# VoltageMonitor.net
KiCad netlist of a schematic drawn in Altium Designer
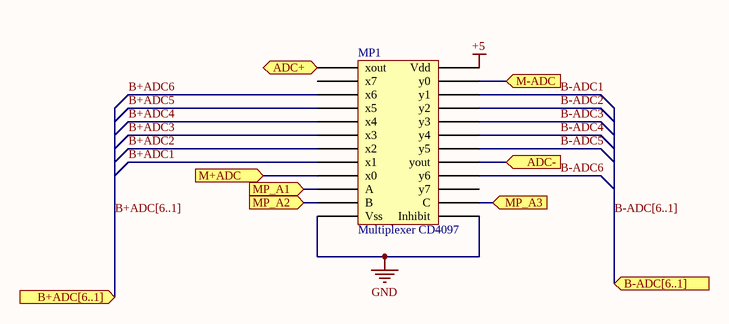
[diagram p0: VoltageMonitor.SchDoc]

(export (version "E")
  (design (tool "Eeschema 10.0.6"))
  (components
    (comp (ref "MP1")
      (value "Multiplexer CD4097")
      (footprint "SOIC24")
      (libsource (lib "Custom") (part "Multiplexer CD4097"))
    )
  )
  (nets
    (net (code "1") (name "+5") (class "Default")
      (node (ref "MP1") (pin "Vdd") (pinfunction "Vdd_Vdd") (pintype "passive"))
    )
    (net (code "2") (name "/ADC+") (class "Default")
      (node (ref "MP1") (pin "xout") (pinfunction "xout_xout") (pintype "passive"))
    )
    (net (code "3") (name "/ADC-") (class "Default")
      (node (ref "MP1") (pin "yout") (pinfunction "yout_yout") (pintype "passive"))
    )
    (net (code "4") (name "/B+ADC1") (class "Default")
      (node (ref "MP1") (pin "x1") (pinfunction "x1_x1") (pintype "passive"))
    )
    (net (code "5") (name "/B+ADC2") (class "Default")
      (node (ref "MP1") (pin "x2") (pinfunction "x2_x2") (pintype "passive"))
    )
    (net (code "6") (name "/B+ADC3") (class "Default")
      (node (ref "MP1") (pin "x3") (pinfunction "x3_x3") (pintype "passive"))
    )
    (net (code "7") (name "/B+ADC4") (class "Default")
      (node (ref "MP1") (pin "x4") (pinfunction "x4_x4") (pintype "passive"))
    )
    (net (code "8") (name "/B+ADC5") (class "Default")
      (node (ref "MP1") (pin "x5") (pinfunction "x5_x5") (pintype "passive"))
    )
    (net (code "9") (name "/B+ADC6") (class "Default")
      (node (ref "MP1") (pin "x6") (pinfunction "x6_x6") (pintype "passive"))
    )
    (net (code "11") (name "/B-ADC1") (class "Default")
      (node (ref "MP1") (pin "y1") (pinfunction "y1_y1") (pintype "passive"))
    )
    (net (code "12") (name "/B-ADC2") (class "Default")
      (node (ref "MP1") (pin "y2") (pinfunction "y2_y2") (pintype "passive"))
    )
    (net (code "13") (name "/B-ADC3") (class "Default")
      (node (ref "MP1") (pin "y3") (pinfunction "y3_y3") (pintype "passive"))
    )
    (net (code "14") (name "/B-ADC4") (class "Default")
      (node (ref "MP1") (pin "y4") (pinfunction "y4_y4") (pintype "passive"))
    )
    (net (code "15") (name "/B-ADC5") (class "Default")
      (node (ref "MP1") (pin "y5") (pinfunction "y5_y5") (pintype "passive"))
    )
    (net (code "16") (name "/B-ADC6") (class "Default")
      (node (ref "MP1") (pin "y6") (pinfunction "y6_y6") (pintype "passive"))
    )
    (net (code "18") (name "/M+ADC") (class "Default")
      (node (ref "MP1") (pin "x0") (pinfunction "x0_x0") (pintype "passive"))
    )
    (net (code "19") (name "/M-ADC") (class "Default")
      (node (ref "MP1") (pin "y0") (pinfunction "y0_y0") (pintype "passive"))
    )
    (net (code "20") (name "/MP_A1") (class "Default")
      (node (ref "MP1") (pin "A") (pinfunction "A_A") (pintype "passive"))
    )
    (net (code "21") (name "/MP_A2") (class "Default")
      (node (ref "MP1") (pin "B") (pinfunction "B_B") (pintype "passive"))
    )
    (net (code "22") (name "/MP_A3") (class "Default")
      (node (ref "MP1") (pin "C") (pinfunction "C_C") (pintype "passive"))
    )
    (net (code "23") (name "GND") (class "Default")
      (node (ref "MP1") (pin "Inhibit") (pinfunction "Inhibit_Inhibit") (pintype "passive"))
      (node (ref "MP1") (pin "Vss") (pinfunction "Vss_Vss") (pintype "passive"))
    )
    (net (code "24") (name "unconnected-(MP1-Padx7)") (class "Default")
      (node (ref "MP1") (pin "x7") (pinfunction "x7_x7") (pintype "passive"))
    )
    (net (code "25") (name "unconnected-(MP1-Pady7)") (class "Default")
      (node (ref "MP1") (pin "y7") (pinfunction "y7_y7") (pintype "passive"))
    )
  )
)
